# Storage.net
KiCad netlist of a schematic drawn in Altium Designer
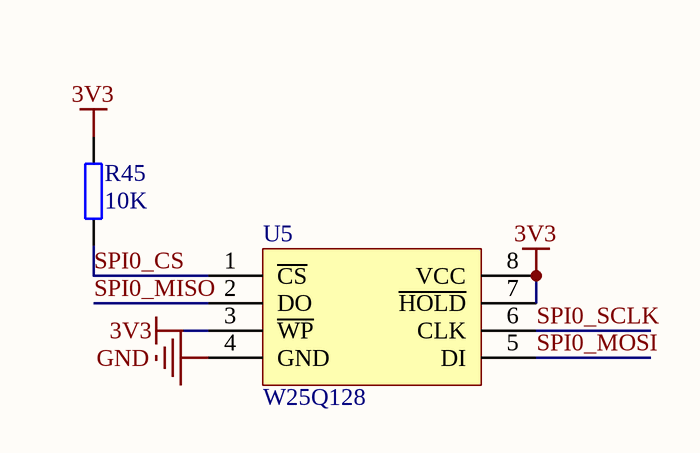
[diagram p0: Storage.SchDoc]

(export (version "E")
  (design (tool "Eeschema 10.0.6"))
  (components
    (comp (ref "R45")
      (value "10K")
      (footprint "RES-0603")
      (description "贴片电阻0603")
      (fields (field (name "TOLERANCE") "5%") (field (name "VOLTAGE") "50V"))
      (libsource (lib "momo") (part "R_0603"))
    )
    (comp (ref "U5")
      (value "W25Q128")
      (footprint "LC-SOP-8_208mil")
      (description "128Mbits SPI Flash")
      (libsource (lib "momo") (part "W25Q128"))
    )
  )
  (nets
    (net (code "1") (name "/SPI0_CS") (class "Default")
      (node (ref "R45") (pin "1") (pinfunction "1_1") (pintype "passive"))
      (node (ref "U5") (pin "1") (pinfunction "~{CS}_1") (pintype "passive"))
    )
    (net (code "2") (name "/SPI0_MISO") (class "Default")
      (node (ref "U5") (pin "2") (pinfunction "DO_2") (pintype "passive"))
    )
    (net (code "3") (name "/SPI0_MOSI") (class "Default")
      (node (ref "U5") (pin "5") (pinfunction "DI_5") (pintype "passive"))
    )
    (net (code "4") (name "/SPI0_SCLK") (class "Default")
      (node (ref "U5") (pin "6") (pinfunction "CLK_6") (pintype "passive"))
    )
    (net (code "5") (name "3V3") (class "Default")
      (node (ref "R45") (pin "2") (pinfunction "2_2") (pintype "passive"))
      (node (ref "U5") (pin "3") (pinfunction "~{WP}_3") (pintype "passive"))
      (node (ref "U5") (pin "7") (pinfunction "~{HOLD}_7") (pintype "passive"))
      (node (ref "U5") (pin "8") (pinfunction "VCC_8") (pintype "passive"))
    )
    (net (code "6") (name "GND") (class "Default")
      (node (ref "U5") (pin "4") (pinfunction "GND_4") (pintype "passive"))
    )
  )
)
